# PowerSupply.net
KiCad netlist of a schematic drawn in Altium Designer
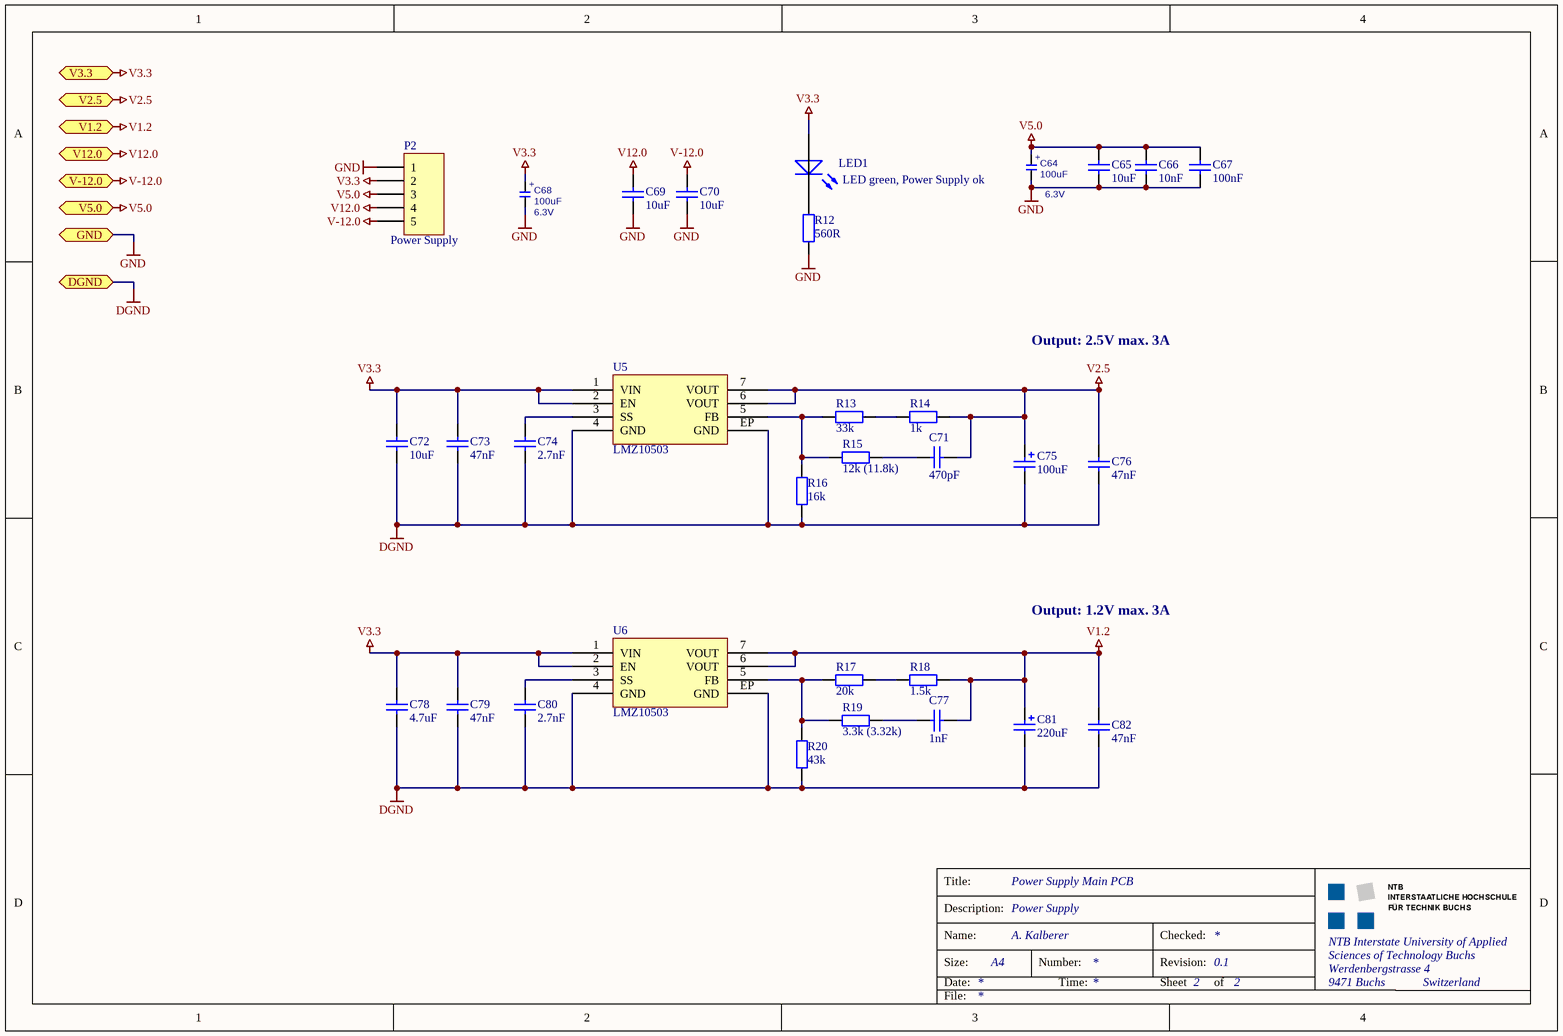
[diagram p0: PowerSupply.SchDoc]

(export (version "E")
  (design (tool "Eeschema 10.0.6"))
  (components
    (comp (ref "C64")
      (value "100uF")
      (footprint "1206_Pol")
      (description "Capacitor TA 100uF 10V 20% 3528")
      (fields
        (field (name "TOLERANCE") "20%")
        (field (name "RATING") "6.3V")
        (field (name "MANUFACTURER") "Generic")
      )
      (libsource (lib "Viola") (part "C-TA-100uF-10V-20%-3528"))
    )
    (comp (ref "C65")
      (value "10uF")
      (footprint "1206")
      (description "Capacitor")
      (fields (field (name "#PUBLISHER") "Dr. A. Heinzelmann"))
      (libsource (lib "EFS_Sensorboard") (part "C"))
    )
    (comp (ref "C66")
      (value "10nF")
      (footprint "0603_3D")
      (description "Capacitor")
      (fields (field (name "#PUBLISHER") "Dr. A. Heinzelmann"))
      (libsource (lib "EFS_Sensorboard") (part "C"))
    )
    (comp (ref "C67")
      (value "100nF")
      (footprint "0603_3D")
      (description "Capacitor")
      (fields (field (name "#PUBLISHER") "Dr. A. Heinzelmann"))
      (libsource (lib "EFS_Sensorboard") (part "C"))
    )
    (comp (ref "C68")
      (value "100uF")
      (footprint "1206_Pol")
      (description "Capacitor TA 100uF 10V 20% 3528")
      (fields
        (field (name "TOLERANCE") "20%")
        (field (name "RATING") "6.3V")
        (field (name "MANUFACTURER") "Generic")
      )
      (libsource (lib "Viola") (part "C-TA-100uF-10V-20%-3528"))
    )
    (comp (ref "C69")
      (value "10uF")
      (footprint "1206")
      (description "Capacitor")
      (fields (field (name "#PUBLISHER") "Dr. A. Heinzelmann"))
      (libsource (lib "EFS_Sensorboard") (part "C"))
    )
    (comp (ref "C70")
      (value "10uF")
      (footprint "1206")
      (description "Capacitor")
      (fields (field (name "#PUBLISHER") "Dr. A. Heinzelmann"))
      (libsource (lib "EFS_Sensorboard") (part "C"))
    )
    (comp (ref "C71")
      (value "470pF")
      (footprint "0603_3D")
      (description "Capacitor")
      (fields (field (name "#PUBLISHER") "Dr. A. Heinzelmann"))
      (libsource (lib "EFS_Sensorboard") (part "C"))
    )
    (comp (ref "C72")
      (value "10uF")
      (footprint "1206")
      (description "Capacitor")
      (fields (field (name "#PUBLISHER") "Dr. A. Heinzelmann"))
      (libsource (lib "EFS_Sensorboard") (part "C"))
    )
    (comp (ref "C73")
      (value "47nF")
      (footprint "0603_3D")
      (description "Capacitor")
      (fields (field (name "#PUBLISHER") "Dr. A. Heinzelmann"))
      (libsource (lib "EFS_Sensorboard") (part "C"))
    )
    (comp (ref "C74")
      (value "2.7nF")
      (footprint "0603_3D")
      (description "Capacitor")
      (fields (field (name "#PUBLISHER") "Dr. A. Heinzelmann"))
      (libsource (lib "EFS_Sensorboard") (part "C"))
    )
    (comp (ref "C75")
      (value "100uF")
      (footprint "1812_Pol")
      (description "Polarized Capacitor Positive Mark Bar")
      (fields (field (name "#PUBLISHER") "Dr. A. Heinzelmann"))
      (libsource (lib "ELE-LIB") (part "C_POL"))
    )
    (comp (ref "C76")
      (value "47nF")
      (footprint "0603_3D")
      (description "Capacitor")
      (fields (field (name "#PUBLISHER") "Dr. A. Heinzelmann"))
      (libsource (lib "EFS_Sensorboard") (part "C"))
    )
    (comp (ref "C77")
      (value "1nF")
      (footprint "0603_3D")
      (description "Capacitor")
      (fields (field (name "#PUBLISHER") "Dr. A. Heinzelmann"))
      (libsource (lib "EFS_Sensorboard") (part "C"))
    )
    (comp (ref "C78")
      (value "4.7uF")
      (footprint "1206")
      (description "Capacitor")
      (fields (field (name "#PUBLISHER") "Dr. A. Heinzelmann"))
      (libsource (lib "EFS_Sensorboard") (part "C"))
    )
    (comp (ref "C79")
      (value "47nF")
      (footprint "0603_3D")
      (description "Capacitor")
      (fields (field (name "#PUBLISHER") "Dr. A. Heinzelmann"))
      (libsource (lib "EFS_Sensorboard") (part "C"))
    )
    (comp (ref "C80")
      (value "2.7nF")
      (footprint "0603_3D")
      (description "Capacitor")
      (fields (field (name "#PUBLISHER") "Dr. A. Heinzelmann"))
      (libsource (lib "EFS_Sensorboard") (part "C"))
    )
    (comp (ref "C81")
      (value "220uF")
      (footprint "CC-Type-B-3528")
      (description "Polarized Capacitor Positive Mark Bar")
      (fields (field (name "#PUBLISHER") "Dr. A. Heinzelmann"))
      (libsource (lib "ELE-LIB") (part "C_POL"))
    )
    (comp (ref "C82")
      (value "47nF")
      (footprint "0603_3D")
      (description "Capacitor")
      (fields (field (name "#PUBLISHER") "Dr. A. Heinzelmann"))
      (libsource (lib "EFS_Sensorboard") (part "C"))
    )
    (comp (ref "LED1")
      (value "LED green, Power Supply ok")
      (footprint "0805")
      (description "Typical RED, GREEN, YELLOW, AMBER GaAs LED")
      (fields (field (name "#PUBLISHER") "Dr. A. Heinzelmann"))
      (libsource (lib "ELE-LIB") (part "LED"))
    )
    (comp (ref "P2")
      (value "Power Supply")
      (footprint "Header - 1x5 - H")
      (description "Header, 5-Pin")
      (fields (field (name "PUBLISHER") "Altium Limited"))
      (libsource (lib "inf") (part "Header 1x5"))
    )
    (comp (ref "R12")
      (value "560R")
      (footprint "0603_3D")
      (description "Resistor")
      (fields (field (name "#PUBLISHER") "Dr. A. Heinzelmann"))
      (libsource (lib "") (part "R_1"))
    )
    (comp (ref "R13")
      (value "33k")
      (footprint "0603_3D")
      (description "Resistor")
      (fields (field (name "#PUBLISHER") "Dr. A. Heinzelmann"))
      (libsource (lib "ELE-LIB") (part "R"))
    )
    (comp (ref "R14")
      (value "1k")
      (footprint "0603_3D")
      (description "Resistor")
      (fields (field (name "#PUBLISHER") "Dr. A. Heinzelmann"))
      (libsource (lib "ELE-LIB") (part "R"))
    )
    (comp (ref "R15")
      (value "12k (11.8k)")
      (footprint "0603_3D")
      (description "Resistor")
      (fields (field (name "#PUBLISHER") "Dr. A. Heinzelmann"))
      (libsource (lib "ELE-LIB") (part "R"))
    )
    (comp (ref "R16")
      (value "16k")
      (footprint "0603_3D")
      (description "Resistor")
      (fields (field (name "#PUBLISHER") "Dr. A. Heinzelmann"))
      (libsource (lib "") (part "R_2"))
    )
    (comp (ref "R17")
      (value "20k")
      (footprint "0603_3D")
      (description "Resistor")
      (fields (field (name "#PUBLISHER") "Dr. A. Heinzelmann"))
      (libsource (lib "ELE-LIB") (part "R"))
    )
    (comp (ref "R18")
      (value "1.5k")
      (footprint "0603_3D")
      (description "Resistor")
      (fields (field (name "#PUBLISHER") "Dr. A. Heinzelmann"))
      (libsource (lib "ELE-LIB") (part "R"))
    )
    (comp (ref "R19")
      (value "3.3k (3.32k)")
      (footprint "0603_3D")
      (description "Resistor")
      (fields (field (name "#PUBLISHER") "Dr. A. Heinzelmann"))
      (libsource (lib "ELE-LIB") (part "R"))
    )
    (comp (ref "R20")
      (value "43k")
      (footprint "0603_3D")
      (description "Resistor")
      (fields (field (name "#PUBLISHER") "Dr. A. Heinzelmann"))
      (libsource (lib "") (part "R_2"))
    )
    (comp (ref "U5")
      (value "LMZ10503")
      (footprint "TZA07A")
      (description "Buck Converter")
      (libsource (lib "EFSSensorboard_1") (part "LMZ10503"))
    )
    (comp (ref "U6")
      (value "LMZ10503")
      (footprint "TZA07A")
      (description "Buck Converter")
      (libsource (lib "EFSSensorboard_1") (part "LMZ10503"))
    )
  )
  (nets
    (net (code "1") (name "DGND") (class "Default")
      (node (ref "C72") (pin "1") (pinfunction "1_1") (pintype "passive"))
      (node (ref "C73") (pin "1") (pinfunction "1_1") (pintype "passive"))
      (node (ref "C74") (pin "1") (pinfunction "1_1") (pintype "passive"))
      (node (ref "C75") (pin "2") (pinfunction "Neg_2") (pintype "passive"))
      (node (ref "C76") (pin "1") (pinfunction "1_1") (pintype "passive"))
      (node (ref "C78") (pin "1") (pinfunction "1_1") (pintype "passive"))
      (node (ref "C79") (pin "1") (pinfunction "1_1") (pintype "passive"))
      (node (ref "C80") (pin "1") (pinfunction "1_1") (pintype "passive"))
      (node (ref "C81") (pin "2") (pinfunction "Neg_2") (pintype "passive"))
      (node (ref "C82") (pin "1") (pinfunction "1_1") (pintype "passive"))
      (node (ref "R16") (pin "2") (pinfunction "2_2") (pintype "passive"))
      (node (ref "R20") (pin "2") (pinfunction "2_2") (pintype "passive"))
      (node (ref "U5") (pin "4") (pinfunction "GND_4") (pintype "passive"))
      (node (ref "U5") (pin "EP") (pinfunction "GND_EP") (pintype "passive"))
      (node (ref "U6") (pin "4") (pinfunction "GND_4") (pintype "passive"))
      (node (ref "U6") (pin "EP") (pinfunction "GND_EP") (pintype "passive"))
    )
    (net (code "2") (name "GND") (class "Default")
      (node (ref "C64") (pin "2") (pinfunction "2_2") (pintype "passive"))
      (node (ref "C65") (pin "1") (pinfunction "1_1") (pintype "passive"))
      (node (ref "C66") (pin "1") (pinfunction "1_1") (pintype "passive"))
      (node (ref "C67") (pin "1") (pinfunction "1_1") (pintype "passive"))
      (node (ref "C68") (pin "2") (pinfunction "2_2") (pintype "passive"))
      (node (ref "C69") (pin "1") (pinfunction "1_1") (pintype "passive"))
      (node (ref "C70") (pin "1") (pinfunction "1_1") (pintype "passive"))
      (node (ref "P2") (pin "1") (pinfunction "1_1") (pintype "passive"))
      (node (ref "R12") (pin "1") (pinfunction "1_1") (pintype "passive"))
    )
    (net (code "3") (name "Net-(C71-Pad2)") (class "Default")
      (node (ref "C71") (pin "2") (pinfunction "2_2") (pintype "passive"))
      (node (ref "R15") (pin "2") (pinfunction "2_2") (pintype "passive"))
    )
    (net (code "4") (name "Net-(C77-Pad2)") (class "Default")
      (node (ref "C77") (pin "2") (pinfunction "2_2") (pintype "passive"))
      (node (ref "R19") (pin "2") (pinfunction "2_2") (pintype "passive"))
    )
    (net (code "5") (name "Net-(LED1-K)") (class "Default")
      (node (ref "LED1") (pin "1") (pinfunction "K_1") (pintype "passive"))
      (node (ref "R12") (pin "2") (pinfunction "2_2") (pintype "passive"))
    )
    (net (code "6") (name "Net-(R13-Pad2)") (class "Default")
      (node (ref "R13") (pin "2") (pinfunction "2_2") (pintype "passive"))
      (node (ref "R14") (pin "1") (pinfunction "1_1") (pintype "passive"))
    )
    (net (code "7") (name "Net-(R17-Pad2)") (class "Default")
      (node (ref "R17") (pin "2") (pinfunction "2_2") (pintype "passive"))
      (node (ref "R18") (pin "1") (pinfunction "1_1") (pintype "passive"))
    )
    (net (code "8") (name "Net-(U5-FB)") (class "Default")
      (node (ref "R13") (pin "1") (pinfunction "1_1") (pintype "passive"))
      (node (ref "R15") (pin "1") (pinfunction "1_1") (pintype "passive"))
      (node (ref "R16") (pin "1") (pinfunction "1_1") (pintype "passive"))
      (node (ref "U5") (pin "5") (pinfunction "FB_5") (pintype "passive"))
    )
    (net (code "9") (name "Net-(U5-SS)") (class "Default")
      (node (ref "C74") (pin "2") (pinfunction "2_2") (pintype "passive"))
      (node (ref "U5") (pin "3") (pinfunction "SS_3") (pintype "passive"))
    )
    (net (code "10") (name "Net-(U6-FB)") (class "Default")
      (node (ref "R17") (pin "1") (pinfunction "1_1") (pintype "passive"))
      (node (ref "R19") (pin "1") (pinfunction "1_1") (pintype "passive"))
      (node (ref "R20") (pin "1") (pinfunction "1_1") (pintype "passive"))
      (node (ref "U6") (pin "5") (pinfunction "FB_5") (pintype "passive"))
    )
    (net (code "11") (name "Net-(U6-SS)") (class "Default")
      (node (ref "C80") (pin "2") (pinfunction "2_2") (pintype "passive"))
      (node (ref "U6") (pin "3") (pinfunction "SS_3") (pintype "passive"))
    )
    (net (code "12") (name "V-12.0") (class "Default")
      (node (ref "C70") (pin "2") (pinfunction "2_2") (pintype "passive"))
      (node (ref "P2") (pin "5") (pinfunction "5_5") (pintype "passive"))
    )
    (net (code "13") (name "V1.2") (class "Default")
      (node (ref "C77") (pin "1") (pinfunction "1_1") (pintype "passive"))
      (node (ref "C81") (pin "1") (pinfunction "Pos_1") (pintype "passive"))
      (node (ref "C82") (pin "2") (pinfunction "2_2") (pintype "passive"))
      (node (ref "R18") (pin "2") (pinfunction "2_2") (pintype "passive"))
      (node (ref "U6") (pin "6") (pinfunction "VOUT_6") (pintype "passive"))
      (node (ref "U6") (pin "7") (pinfunction "VOUT_7") (pintype "passive"))
    )
    (net (code "14") (name "V2.5") (class "Default")
      (node (ref "C71") (pin "1") (pinfunction "1_1") (pintype "passive"))
      (node (ref "C75") (pin "1") (pinfunction "Pos_1") (pintype "passive"))
      (node (ref "C76") (pin "2") (pinfunction "2_2") (pintype "passive"))
      (node (ref "R14") (pin "2") (pinfunction "2_2") (pintype "passive"))
      (node (ref "U5") (pin "6") (pinfunction "VOUT_6") (pintype "passive"))
      (node (ref "U5") (pin "7") (pinfunction "VOUT_7") (pintype "passive"))
    )
    (net (code "15") (name "V3.3") (class "Default")
      (node (ref "C68") (pin "1") (pinfunction "1_1") (pintype "passive"))
      (node (ref "C72") (pin "2") (pinfunction "2_2") (pintype "passive"))
      (node (ref "C73") (pin "2") (pinfunction "2_2") (pintype "passive"))
      (node (ref "C78") (pin "2") (pinfunction "2_2") (pintype "passive"))
      (node (ref "C79") (pin "2") (pinfunction "2_2") (pintype "passive"))
      (node (ref "LED1") (pin "2") (pinfunction "A_2") (pintype "passive"))
      (node (ref "P2") (pin "2") (pinfunction "2_2") (pintype "passive"))
      (node (ref "U5") (pin "1") (pinfunction "VIN_1") (pintype "passive"))
      (node (ref "U5") (pin "2") (pinfunction "EN_2") (pintype "passive"))
      (node (ref "U6") (pin "1") (pinfunction "VIN_1") (pintype "passive"))
      (node (ref "U6") (pin "2") (pinfunction "EN_2") (pintype "passive"))
    )
    (net (code "16") (name "V5.0") (class "Default")
      (node (ref "C64") (pin "1") (pinfunction "1_1") (pintype "passive"))
      (node (ref "C65") (pin "2") (pinfunction "2_2") (pintype "passive"))
      (node (ref "C66") (pin "2") (pinfunction "2_2") (pintype "passive"))
      (node (ref "C67") (pin "2") (pinfunction "2_2") (pintype "passive"))
      (node (ref "P2") (pin "3") (pinfunction "3_3") (pintype "passive"))
    )
    (net (code "17") (name "V12.0") (class "Default")
      (node (ref "C69") (pin "2") (pinfunction "2_2") (pintype "passive"))
      (node (ref "P2") (pin "4") (pinfunction "4_4") (pintype "passive"))
    )
  )
)
